# BigBoard.net
KiCad netlist of a schematic drawn in Altium Designer
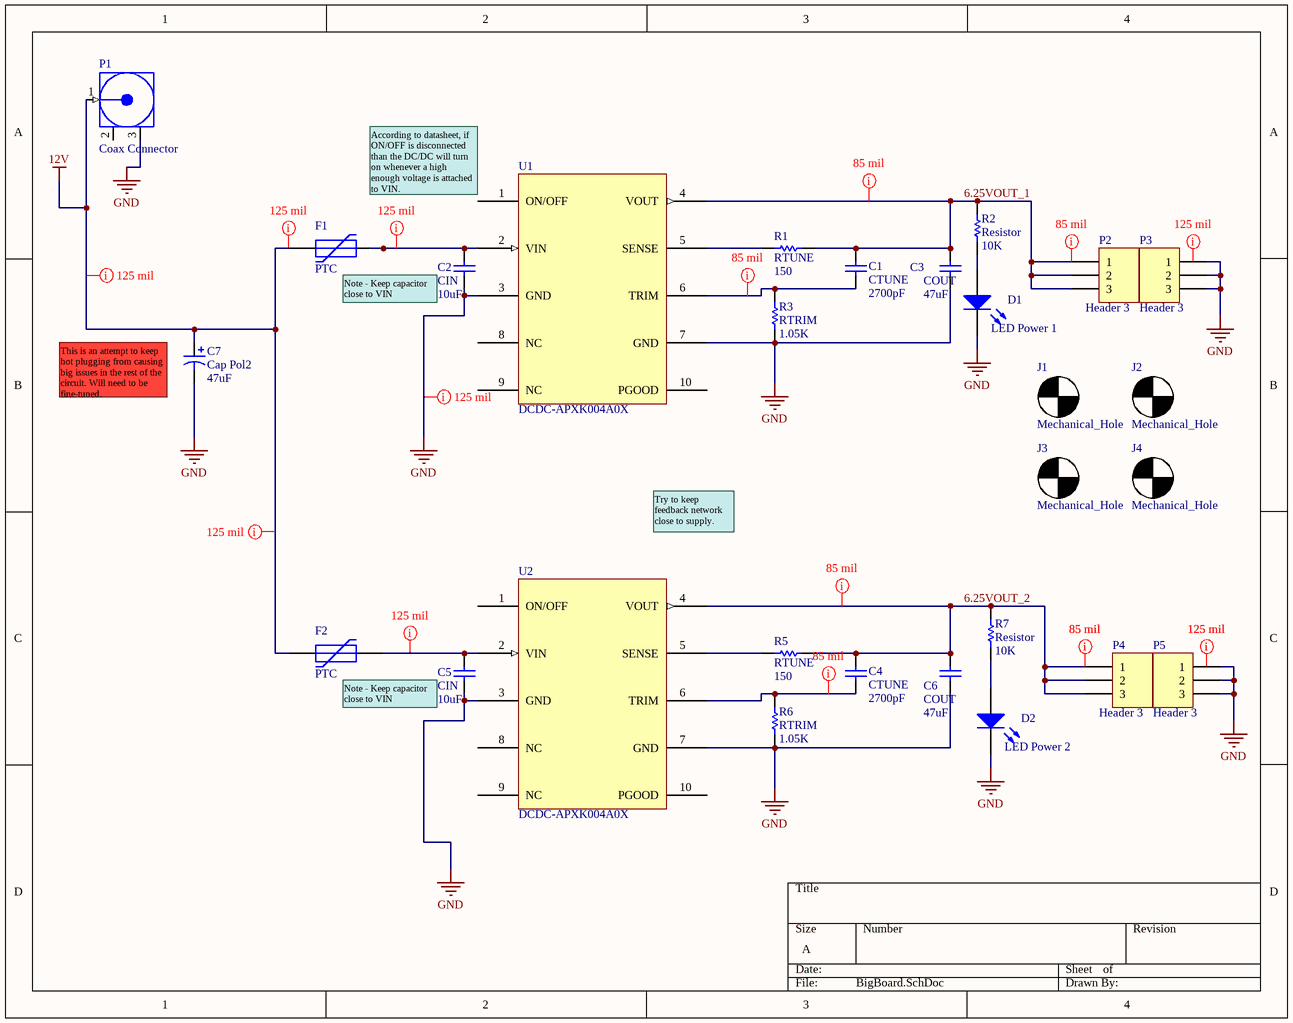
[diagram p0: BigBoard.SchDoc]

(export (version "E")
  (design (tool "Eeschema 10.0.6"))
  (components
    (comp (ref "C1")
      (value "CTUNE")
      (footprint "CAPC1608L")
      (description "Capacitor")
      (fields (field (name "ALTIUM_VALUE") "2700pF") (field (name "PUBLISHER") "Altium Limited"))
      (libsource (lib "mrone") (part "Cap"))
    )
    (comp (ref "C2")
      (value "CIN")
      (footprint "CAPC2012L")
      (description "Capacitor")
      (fields (field (name "ALTIUM_VALUE") "10uF") (field (name "PUBLISHER") "Altium Limited"))
      (libsource (lib "mrone") (part "Cap"))
    )
    (comp (ref "C3")
      (value "COUT")
      (footprint "CAPC3216L")
      (description "Capacitor")
      (fields (field (name "ALTIUM_VALUE") "47uF") (field (name "PUBLISHER") "Altium Limited"))
      (libsource (lib "mrone") (part "Cap"))
    )
    (comp (ref "C4")
      (value "CTUNE")
      (footprint "CAPC1608L")
      (description "Capacitor")
      (fields (field (name "ALTIUM_VALUE") "2700pF") (field (name "PUBLISHER") "Altium Limited"))
      (libsource (lib "mrone") (part "Cap"))
    )
    (comp (ref "C5")
      (value "CIN")
      (footprint "CAPC2012L")
      (description "Capacitor")
      (fields (field (name "ALTIUM_VALUE") "10uF") (field (name "PUBLISHER") "Altium Limited"))
      (libsource (lib "mrone") (part "Cap"))
    )
    (comp (ref "C6")
      (value "COUT")
      (footprint "CAPC3216L")
      (description "Capacitor")
      (fields (field (name "ALTIUM_VALUE") "47uF") (field (name "PUBLISHER") "Altium Limited"))
      (libsource (lib "mrone") (part "Cap"))
    )
    (comp (ref "C7")
      (value "Cap Pol2")
      (footprint "RAD-POLAR-0.1")
      (description "Polarized Capacitor (Axial)")
      (fields (field (name "ALTIUM_VALUE") "47uF") (field (name "PUBLISHER") "Altium Limited"))
      (libsource (lib "mrone") (part "Cap Pol2"))
    )
    (comp (ref "D1")
      (value "LED Power 1")
      (footprint "SurfaceMount(603)")
      (libsource (lib "mrone") (part "LED"))
    )
    (comp (ref "D2")
      (value "LED Power 2")
      (footprint "SurfaceMount(603)")
      (libsource (lib "mrone") (part "LED"))
    )
    (comp (ref "F1")
      (value "PTC")
      (footprint "J1-1812")
      (description "Fuse")
      (fields (field (name "PUBLISHER") "Altium Limited"))
      (libsource (lib "mrone") (part "PTC_FUSE"))
    )
    (comp (ref "F2")
      (value "PTC")
      (footprint "J1-1812")
      (description "Fuse")
      (fields (field (name "PUBLISHER") "Altium Limited"))
      (libsource (lib "mrone") (part "PTC_FUSE"))
    )
    (comp (ref "J1")
      (value "Mechanical_Hole")
      (footprint "#4_Screw_Hole")
      (description "A mechanical hole for mounting the board")
      (libsource (lib "mrone") (part "Mechanical_Hole"))
    )
    (comp (ref "J2")
      (value "Mechanical_Hole")
      (footprint "#4_Screw_Hole")
      (description "A mechanical hole for mounting the board")
      (libsource (lib "mrone") (part "Mechanical_Hole"))
    )
    (comp (ref "J3")
      (value "Mechanical_Hole")
      (footprint "#4_Screw_Hole")
      (description "A mechanical hole for mounting the board")
      (libsource (lib "mrone") (part "Mechanical_Hole"))
    )
    (comp (ref "J4")
      (value "Mechanical_Hole")
      (footprint "#4_Screw_Hole")
      (description "A mechanical hole for mounting the board")
      (libsource (lib "mrone") (part "Mechanical_Hole"))
    )
    (comp (ref "P1")
      (value "Coax Connector")
      (footprint "COAX_3pin")
      (libsource (lib "mrone") (part "COAX-M-3pin"))
    )
    (comp (ref "P2")
      (value "Header 3")
      (footprint "Euroblock-A98334")
      (description "Header, 3-Pin")
      (fields (field (name "PUBLISHER") "Altium Limited"))
      (libsource (lib "mrone") (part "Header 3"))
    )
    (comp (ref "P3")
      (value "Header 3")
      (footprint "Euroblock-A98334")
      (description "Header, 3-Pin")
      (fields (field (name "PUBLISHER") "Altium Limited"))
      (libsource (lib "") (part "Header 3_1"))
    )
    (comp (ref "P4")
      (value "Header 3")
      (footprint "Euroblock-A98334")
      (description "Header, 3-Pin")
      (fields (field (name "PUBLISHER") "Altium Limited"))
      (libsource (lib "mrone") (part "Header 3"))
    )
    (comp (ref "P5")
      (value "Header 3")
      (footprint "Euroblock-A98334")
      (description "Header, 3-Pin")
      (fields (field (name "PUBLISHER") "Altium Limited"))
      (libsource (lib "") (part "Header 3_1"))
    )
    (comp (ref "R1")
      (value "RTUNE")
      (footprint "J1-0603")
      (description "Resistor")
      (fields (field (name "ALTIUM_VALUE") "150") (field (name "PUBLISHER") "Altium Limited"))
      (libsource (lib "mrone") (part "Resistor"))
    )
    (comp (ref "R2")
      (value "Resistor")
      (footprint "J1-0603")
      (fields (field (name "ALTIUM_VALUE") "10K") (field (name "PUBLISHER") "Altium Limited"))
      (libsource (lib "mrone") (part "Resistor"))
    )
    (comp (ref "R3")
      (value "RTRIM")
      (footprint "J1-0603")
      (description "Resistor")
      (fields (field (name "ALTIUM_VALUE") "1.05K") (field (name "PUBLISHER") "Altium Limited"))
      (libsource (lib "mrone") (part "Resistor"))
    )
    (comp (ref "R5")
      (value "RTUNE")
      (footprint "J1-0603")
      (description "Resistor")
      (fields (field (name "ALTIUM_VALUE") "150") (field (name "PUBLISHER") "Altium Limited"))
      (libsource (lib "mrone") (part "Resistor"))
    )
    (comp (ref "R6")
      (value "RTRIM")
      (footprint "J1-0603")
      (description "Resistor")
      (fields (field (name "ALTIUM_VALUE") "1.05K") (field (name "PUBLISHER") "Altium Limited"))
      (libsource (lib "mrone") (part "Resistor"))
    )
    (comp (ref "R7")
      (value "Resistor")
      (footprint "J1-0603")
      (fields (field (name "ALTIUM_VALUE") "10K") (field (name "PUBLISHER") "Altium Limited"))
      (libsource (lib "mrone") (part "Resistor"))
    )
    (comp (ref "U1")
      (value "DCDC-APXK004A0X")
      (footprint "DCDC-APXK004A0X")
      (description "DC/DC converter for the rone charger")
      (libsource (lib "mrone") (part "DCDC-APXK004A0X"))
    )
    (comp (ref "U2")
      (value "DCDC-APXK004A0X")
      (footprint "DCDC-APXK004A0X")
      (description "DC/DC converter for the rone charger")
      (libsource (lib "mrone") (part "DCDC-APXK004A0X"))
    )
  )
  (nets
    (net (code "1") (name "/6.25VOUT_1") (class "Default")
      (node (ref "C1") (pin "1") (pinfunction "1_1") (pintype "passive"))
      (node (ref "C3") (pin "2") (pinfunction "2_2") (pintype "passive"))
      (node (ref "P2") (pin "1") (pinfunction "1_1") (pintype "passive"))
      (node (ref "P2") (pin "2") (pinfunction "2_2") (pintype "passive"))
      (node (ref "P2") (pin "3") (pinfunction "3_3") (pintype "passive"))
      (node (ref "R1") (pin "1") (pinfunction "1_1") (pintype "passive"))
      (node (ref "R2") (pin "1") (pinfunction "1_1") (pintype "passive"))
      (node (ref "U1") (pin "4") (pinfunction "VOUT_4") (pintype "output"))
    )
    (net (code "2") (name "/6.25VOUT_2") (class "Default")
      (node (ref "C4") (pin "1") (pinfunction "1_1") (pintype "passive"))
      (node (ref "C6") (pin "2") (pinfunction "2_2") (pintype "passive"))
      (node (ref "P4") (pin "1") (pinfunction "1_1") (pintype "passive"))
      (node (ref "P4") (pin "2") (pinfunction "2_2") (pintype "passive"))
      (node (ref "P4") (pin "3") (pinfunction "3_3") (pintype "passive"))
      (node (ref "R5") (pin "1") (pinfunction "1_1") (pintype "passive"))
      (node (ref "R7") (pin "1") (pinfunction "1_1") (pintype "passive"))
      (node (ref "U2") (pin "4") (pinfunction "VOUT_4") (pintype "output"))
    )
    (net (code "3") (name "12V") (class "Default")
      (node (ref "C7") (pin "1") (pinfunction "1_1") (pintype "passive"))
      (node (ref "F1") (pin "1") (pinfunction "1_1") (pintype "passive"))
      (node (ref "F2") (pin "1") (pinfunction "1_1") (pintype "passive"))
      (node (ref "P1") (pin "1") (pinfunction "VCC_1") (pintype "input"))
    )
    (net (code "4") (name "GND") (class "Default")
      (node (ref "C2") (pin "1") (pinfunction "1_1") (pintype "passive"))
      (node (ref "C3") (pin "1") (pinfunction "1_1") (pintype "passive"))
      (node (ref "C5") (pin "1") (pinfunction "1_1") (pintype "passive"))
      (node (ref "C6") (pin "1") (pinfunction "1_1") (pintype "passive"))
      (node (ref "C7") (pin "2") (pinfunction "2_2") (pintype "passive"))
      (node (ref "D1") (pin "2") (pinfunction "K_2") (pintype "passive"))
      (node (ref "D2") (pin "2") (pinfunction "K_2") (pintype "passive"))
      (node (ref "P1") (pin "3") (pinfunction "GND_3") (pintype "power_in"))
      (node (ref "P3") (pin "1") (pinfunction "1_1") (pintype "passive"))
      (node (ref "P3") (pin "2") (pinfunction "2_2") (pintype "passive"))
      (node (ref "P3") (pin "3") (pinfunction "3_3") (pintype "passive"))
      (node (ref "P5") (pin "1") (pinfunction "1_1") (pintype "passive"))
      (node (ref "P5") (pin "2") (pinfunction "2_2") (pintype "passive"))
      (node (ref "P5") (pin "3") (pinfunction "3_3") (pintype "passive"))
      (node (ref "R3") (pin "1") (pinfunction "1_1") (pintype "passive"))
      (node (ref "R6") (pin "1") (pinfunction "1_1") (pintype "passive"))
      (node (ref "U1") (pin "3") (pinfunction "GND_3") (pintype "power_in"))
      (node (ref "U1") (pin "7") (pinfunction "GND_7") (pintype "power_in"))
      (node (ref "U2") (pin "3") (pinfunction "GND_3") (pintype "power_in"))
      (node (ref "U2") (pin "7") (pinfunction "GND_7") (pintype "power_in"))
    )
    (net (code "5") (name "Net-(D1-A)") (class "Default")
      (node (ref "D1") (pin "1") (pinfunction "A_1") (pintype "passive"))
      (node (ref "R2") (pin "2") (pinfunction "2_2") (pintype "passive"))
    )
    (net (code "6") (name "Net-(D2-A)") (class "Default")
      (node (ref "D2") (pin "1") (pinfunction "A_1") (pintype "passive"))
      (node (ref "R7") (pin "2") (pinfunction "2_2") (pintype "passive"))
    )
    (net (code "7") (name "Net-(U1-SENSE)") (class "Default")
      (node (ref "R1") (pin "2") (pinfunction "2_2") (pintype "passive"))
      (node (ref "U1") (pin "5") (pinfunction "SENSE_5") (pintype "passive"))
    )
    (net (code "8") (name "Net-(U1-TRIM)") (class "Default")
      (node (ref "C1") (pin "2") (pinfunction "2_2") (pintype "passive"))
      (node (ref "R3") (pin "2") (pinfunction "2_2") (pintype "passive"))
      (node (ref "U1") (pin "6") (pinfunction "TRIM_6") (pintype "passive"))
    )
    (net (code "9") (name "Net-(U1-VIN)") (class "Default")
      (node (ref "C2") (pin "2") (pinfunction "2_2") (pintype "passive"))
      (node (ref "F1") (pin "2") (pinfunction "2_2") (pintype "passive"))
      (node (ref "U1") (pin "2") (pinfunction "VIN_2") (pintype "input"))
    )
    (net (code "10") (name "Net-(U2-SENSE)") (class "Default")
      (node (ref "R5") (pin "2") (pinfunction "2_2") (pintype "passive"))
      (node (ref "U2") (pin "5") (pinfunction "SENSE_5") (pintype "passive"))
    )
    (net (code "11") (name "Net-(U2-TRIM)") (class "Default")
      (node (ref "C4") (pin "2") (pinfunction "2_2") (pintype "passive"))
      (node (ref "R6") (pin "2") (pinfunction "2_2") (pintype "passive"))
      (node (ref "U2") (pin "6") (pinfunction "TRIM_6") (pintype "passive"))
    )
    (net (code "12") (name "Net-(U2-VIN)") (class "Default")
      (node (ref "C5") (pin "2") (pinfunction "2_2") (pintype "passive"))
      (node (ref "F2") (pin "2") (pinfunction "2_2") (pintype "passive"))
      (node (ref "U2") (pin "2") (pinfunction "VIN_2") (pintype "input"))
    )
    (net (code "13") (name "unconnected-(P1-Pad2)") (class "Default")
      (node (ref "P1") (pin "2") (pintype "passive"))
    )
    (net (code "14") (name "unconnected-(U1-NC-Pad8)") (class "Default")
      (node (ref "U1") (pin "8") (pinfunction "NC_8") (pintype "passive"))
    )
    (net (code "15") (name "unconnected-(U1-NC-Pad9)") (class "Default")
      (node (ref "U1") (pin "9") (pinfunction "NC_9") (pintype "passive"))
    )
    (net (code "16") (name "unconnected-(U1-ON{slash}OFF-Pad1)") (class "Default")
      (node (ref "U1") (pin "1") (pinfunction "ON/OFF_1") (pintype "power_in"))
    )
    (net (code "17") (name "unconnected-(U1-PGOOD-Pad10)") (class "Default")
      (node (ref "U1") (pin "10") (pinfunction "PGOOD_10") (pintype "passive"))
    )
    (net (code "18") (name "unconnected-(U2-NC-Pad8)") (class "Default")
      (node (ref "U2") (pin "8") (pinfunction "NC_8") (pintype "passive"))
    )
    (net (code "19") (name "unconnected-(U2-NC-Pad9)") (class "Default")
      (node (ref "U2") (pin "9") (pinfunction "NC_9") (pintype "passive"))
    )
    (net (code "20") (name "unconnected-(U2-ON{slash}OFF-Pad1)") (class "Default")
      (node (ref "U2") (pin "1") (pinfunction "ON/OFF_1") (pintype "power_in"))
    )
    (net (code "21") (name "unconnected-(U2-PGOOD-Pad10)") (class "Default")
      (node (ref "U2") (pin "10") (pinfunction "PGOOD_10") (pintype "passive"))
    )
  )
)
